# driver_ckt_speed.net
KiCad netlist of a schematic drawn in EAGLE
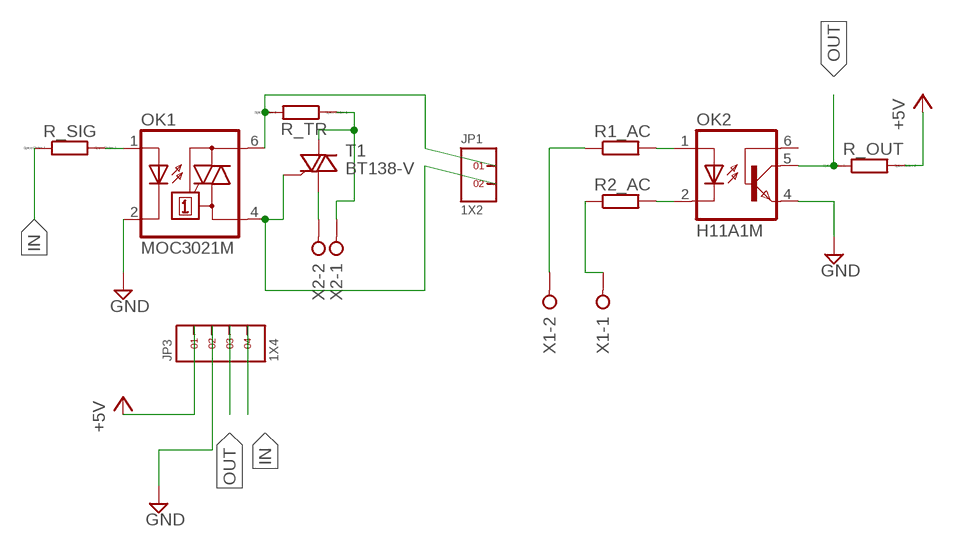
[diagram p0: schematic, sheet 1]

(export (version "E")
  (design (tool "Eeschema 10.0.6"))
  (components
    (comp (ref "JP1")
      (value "1X2")
      (footprint "eagle-import:1X2")
      (libsource (lib "eagle-import") (part "1X2"))
    )
    (comp (ref "JP3")
      (value "1X4")
      (footprint "eagle-import:1X4")
      (libsource (lib "eagle-import") (part "1X4"))
    )
    (comp (ref "OK1")
      (value "MOC3021M")
      (footprint "eagle-import:DIL06")
      (fields (field (name "MF") "FAIRCHILD SEMICONDUCTOR") (field (name "MPN") "MOC3021-M"))
      (libsource (lib "eagle-import") (part "MOC30M21"))
    )
    (comp (ref "OK2")
      (value "H11A1M")
      (footprint "eagle-import:DIL06")
      (fields (field (name "MPN") "H11A1-M"))
      (libsource (lib "eagle-import") (part "H11A?M1"))
    )
    (comp (ref "R1_AC")
      (value "R-EU_0411/15")
      (footprint "eagle-import:0411_15")
      (libsource (lib "eagle-import") (part "R-EU_0411/15"))
    )
    (comp (ref "R2_AC")
      (value "R-EU_0411/15")
      (footprint "eagle-import:0411_15")
      (libsource (lib "eagle-import") (part "R-EU_0411/15"))
    )
    (comp (ref "R_OUT")
      (value "RR1206")
      (footprint "eagle-import:R1206")
      (libsource (lib "eagle-import") (part "RR1206"))
    )
    (comp (ref "R_SIG")
      (value "RR1206")
      (footprint "eagle-import:R1206")
      (libsource (lib "eagle-import") (part "RR1206"))
    )
    (comp (ref "R_TR")
      (value "RR1206")
      (footprint "eagle-import:R1206")
      (libsource (lib "eagle-import") (part "RR1206"))
    )
    (comp (ref "T1")
      (value "BT138-V")
      (footprint "eagle-import:TO220BV")
      (libsource (lib "eagle-import") (part "BT138-V"))
    )
    (comp (ref "X1")
      (value "W237-02P")
      (footprint "eagle-import:W237-132")
      (libsource (lib "eagle-import") (part "W237-02P"))
    )
    (comp (ref "X2")
      (value "W237-02P")
      (footprint "eagle-import:W237-132")
      (libsource (lib "eagle-import") (part "W237-02P"))
    )
  )
  (nets
    (net (code "1") (name "+5V") (class "Default")
      (node (ref "JP3") (pin "1") (pinfunction "1_1") (pintype "bidirectional"))
      (node (ref "R_OUT") (pin "2") (pinfunction "2_2") (pintype "passive"))
    )
    (net (code "2") (name "GND") (class "Default")
      (node (ref "JP3") (pin "2") (pinfunction "2_2") (pintype "bidirectional"))
      (node (ref "OK1") (pin "2") (pinfunction "C_2") (pintype "passive"))
      (node (ref "OK2") (pin "4") (pinfunction "EMI_4") (pintype "passive"))
    )
    (net (code "3") (name "IN") (class "Default")
      (node (ref "JP3") (pin "4") (pinfunction "4_4") (pintype "bidirectional"))
      (node (ref "R_SIG") (pin "1") (pinfunction "1_1") (pintype "passive"))
    )
    (net (code "4") (name "Net-(OK1-A)") (class "Default")
      (node (ref "OK1") (pin "1") (pinfunction "A_1") (pintype "passive"))
      (node (ref "R_SIG") (pin "2") (pinfunction "2_2") (pintype "passive"))
    )
    (net (code "5") (name "Net-(OK1-A1)") (class "Default")
      (node (ref "JP1") (pin "2") (pinfunction "2_2") (pintype "bidirectional"))
      (node (ref "OK1") (pin "4") (pinfunction "A1_4") (pintype "passive"))
      (node (ref "T1") (pin "G") (pinfunction "G_G") (pintype "passive"))
    )
    (net (code "6") (name "Net-(OK1-A2)") (class "Default")
      (node (ref "JP1") (pin "1") (pinfunction "1_1") (pintype "bidirectional"))
      (node (ref "OK1") (pin "6") (pinfunction "A2_6") (pintype "passive"))
      (node (ref "R_TR") (pin "2") (pinfunction "2_2") (pintype "passive"))
    )
    (net (code "7") (name "Net-(OK2-A)") (class "Default")
      (node (ref "OK2") (pin "1") (pinfunction "A_1") (pintype "passive"))
      (node (ref "R1_AC") (pin "2") (pinfunction "2_2") (pintype "passive"))
    )
    (net (code "8") (name "Net-(OK2-C)") (class "Default")
      (node (ref "OK2") (pin "2") (pinfunction "C_2") (pintype "passive"))
      (node (ref "R2_AC") (pin "2") (pinfunction "2_2") (pintype "passive"))
    )
    (net (code "9") (name "Net-(T1-A1)") (class "Default")
      (node (ref "T1") (pin "T1") (pinfunction "A1_T1") (pintype "passive"))
      (node (ref "X2") (pin "2") (pinfunction "KL_2") (pintype "passive"))
    )
    (net (code "10") (name "Net-(T1-A2)") (class "Default")
      (node (ref "R_TR") (pin "1") (pinfunction "1_1") (pintype "passive"))
      (node (ref "T1") (pin "T2") (pinfunction "A2_T2") (pintype "passive"))
      (node (ref "X2") (pin "1") (pinfunction "KL_1") (pintype "passive"))
    )
    (net (code "11") (name "Net-(X1A-KL)") (class "Default")
      (node (ref "R2_AC") (pin "1") (pinfunction "1_1") (pintype "passive"))
      (node (ref "X1") (pin "1") (pinfunction "KL_1") (pintype "passive"))
    )
    (net (code "12") (name "Net-(X1B-KL)") (class "Default")
      (node (ref "R1_AC") (pin "1") (pinfunction "1_1") (pintype "passive"))
      (node (ref "X1") (pin "2") (pinfunction "KL_2") (pintype "passive"))
    )
    (net (code "13") (name "OUT") (class "Default")
      (node (ref "JP3") (pin "3") (pinfunction "3_3") (pintype "bidirectional"))
      (node (ref "OK2") (pin "5") (pinfunction "COL_5") (pintype "passive"))
      (node (ref "R_OUT") (pin "1") (pinfunction "1_1") (pintype "passive"))
    )
    (net (code "14") (name "unconnected-(OK2-BAS-Pad6)") (class "Default")
      (node (ref "OK2") (pin "6") (pinfunction "BAS_6") (pintype "passive"))
    )
  )
)
